# wlpkt1_main.net
KiCad netlist of a schematic drawn in Altium Designer
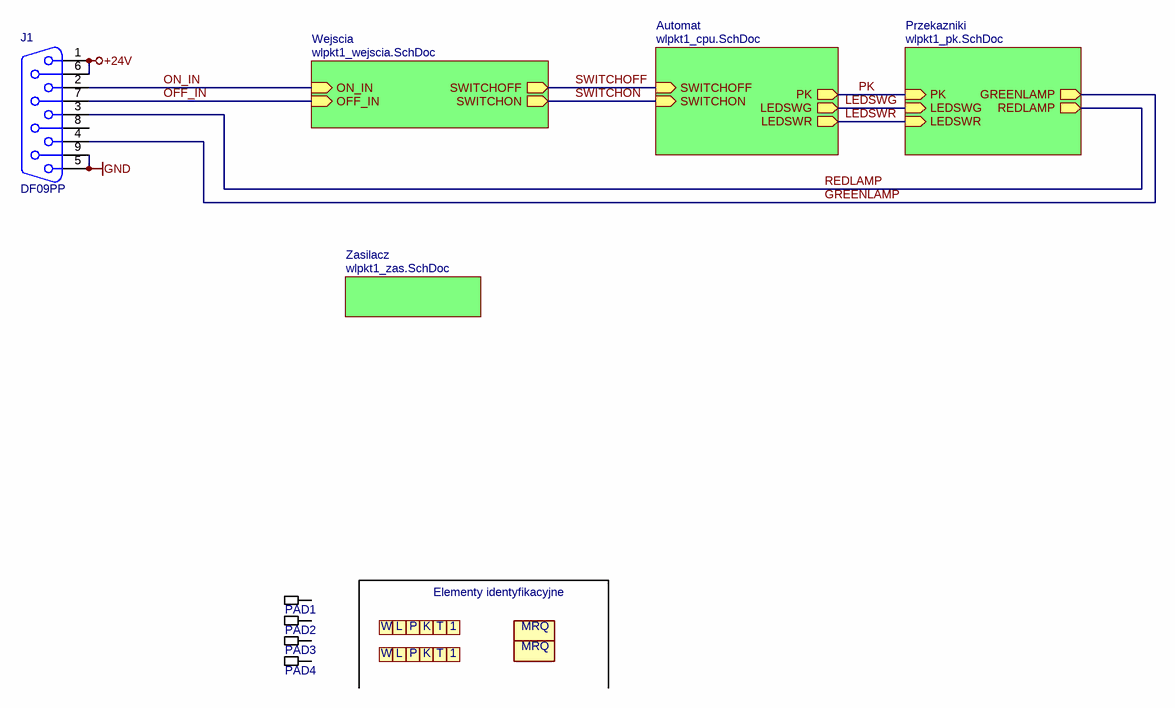
[diagram p0: wlpkt1_main.SchDoc]

(export (version "E")
  (design (tool "Eeschema 10.0.6"))
  (components
    (comp (ref "J1") (value "DF09PP") (footprint "DB9/F") (libsource (lib "PartsMySQL") (part "DB9")))
    (comp (ref "LETTER1")
      (value "LETTERC_W")
      (footprint "LETTERC_W_60_10")
      (libsource (lib "PartsMySQL") (part "LETTERC_W"))
    )
    (comp (ref "LETTER2")
      (value "LETTERC_L")
      (footprint "LETTERC_L_60_10")
      (libsource (lib "PartsMySQL") (part "LETTERC_L"))
    )
    (comp (ref "LETTER3")
      (value "LETTERC_P")
      (footprint "LETTERC_P_60_10")
      (libsource (lib "PartsMySQL") (part "LETTERC_P"))
    )
    (comp (ref "LETTER4")
      (value "LETTERC_K")
      (footprint "LETTERC_K_60_10")
      (libsource (lib "PartsMySQL") (part "LETTERC_K"))
    )
    (comp (ref "LETTER5")
      (value "LETTERC_T")
      (footprint "LETTERC_T_60_10")
      (libsource (lib "PartsMySQL") (part "LETTERC_T"))
    )
    (comp (ref "LETTER6")
      (value "LETTER_1_60_10")
      (footprint "LETTER_1_60_10")
      (libsource (lib "PartsMySQL") (part "LETTER_1"))
    )
    (comp (ref "LETTER7")
      (value "LETTERC_W")
      (footprint "LETTERC_W_60_10")
      (libsource (lib "PartsMySQL") (part "LETTERC_W"))
    )
    (comp (ref "LETTER8")
      (value "LETTERC_L")
      (footprint "LETTERC_L_60_10")
      (libsource (lib "PartsMySQL") (part "LETTERC_L"))
    )
    (comp (ref "LETTER9")
      (value "LETTERC_P")
      (footprint "LETTERC_P_60_10")
      (libsource (lib "PartsMySQL") (part "LETTERC_P"))
    )
    (comp (ref "LETTER10")
      (value "LETTERC_K")
      (footprint "LETTERC_K_60_10")
      (libsource (lib "PartsMySQL") (part "LETTERC_K"))
    )
    (comp (ref "LETTER11")
      (value "LETTERC_T")
      (footprint "LETTERC_T_60_10")
      (libsource (lib "PartsMySQL") (part "LETTERC_T"))
    )
    (comp (ref "LETTER12")
      (value "LETTER_1_60_10")
      (footprint "LETTER_1_60_10")
      (libsource (lib "PartsMySQL") (part "LETTER_1"))
    )
    (comp (ref "LOGO1")
      (value "MRQ_2_8")
      (footprint "MRQ_2_8")
      (libsource (lib "PartsMySQL") (part "MRQLOGO"))
    )
    (comp (ref "LOGO2")
      (value "MRQ_2_8")
      (footprint "MRQ_2_8")
      (libsource (lib "PartsMySQL") (part "MRQLOGO"))
    )
    (comp (ref "PAD1")
      (value "PAD3_5MM")
      (footprint "PAD3_5MM")
      (libsource (lib "PartsMySQL") (part "CLAMP_NOBOM"))
    )
    (comp (ref "PAD2")
      (value "PAD3_5MM")
      (footprint "PAD3_5MM")
      (libsource (lib "PartsMySQL") (part "CLAMP_NOBOM"))
    )
    (comp (ref "PAD3")
      (value "PAD3_5MM")
      (footprint "PAD3_5MM")
      (libsource (lib "PartsMySQL") (part "CLAMP_NOBOM"))
    )
    (comp (ref "PAD4")
      (value "PAD3_5MM")
      (footprint "PAD3_5MM")
      (libsource (lib "PartsMySQL") (part "CLAMP_NOBOM"))
    )
  )
  (nets
    (net (code "1") (name "+24V") (class "Default")
      (node (ref "J1") (pin "1") (pinfunction "1_1") (pintype "passive"))
      (node (ref "J1") (pin "6") (pinfunction "6_6") (pintype "passive"))
    )
    (net (code "2") (name "/GREENLAMP") (class "Default")
      (node (ref "J1") (pin "4") (pinfunction "4_4") (pintype "passive"))
    )
    (net (code "5") (name "/OFF_IN") (class "Default")
      (node (ref "J1") (pin "7") (pinfunction "7_7") (pintype "passive"))
    )
    (net (code "6") (name "/ON_IN") (class "Default")
      (node (ref "J1") (pin "2") (pinfunction "2_2") (pintype "passive"))
    )
    (net (code "8") (name "/REDLAMP") (class "Default")
      (node (ref "J1") (pin "3") (pinfunction "3_3") (pintype "passive"))
    )
    (net (code "11") (name "GND") (class "Default")
      (node (ref "J1") (pin "5") (pinfunction "5_5") (pintype "passive"))
      (node (ref "J1") (pin "9") (pinfunction "9_9") (pintype "passive"))
    )
    (net (code "12") (name "unconnected-(J1-Pad8)") (class "Default")
      (node (ref "J1") (pin "8") (pinfunction "8_8") (pintype "passive"))
    )
    (net (code "13") (name "unconnected-(PAD1-Pad1)") (class "Default")
      (node (ref "PAD1") (pin "1") (pinfunction "1_1") (pintype "passive"))
    )
    (net (code "14") (name "unconnected-(PAD2-Pad1)") (class "Default")
      (node (ref "PAD2") (pin "1") (pinfunction "1_1") (pintype "passive"))
    )
    (net (code "15") (name "unconnected-(PAD3-Pad1)") (class "Default")
      (node (ref "PAD3") (pin "1") (pinfunction "1_1") (pintype "passive"))
    )
    (net (code "16") (name "unconnected-(PAD4-Pad1)") (class "Default")
      (node (ref "PAD4") (pin "1") (pinfunction "1_1") (pintype "passive"))
    )
  )
)
